# Servos_controller.net
KiCad netlist of a schematic drawn in Altium Designer
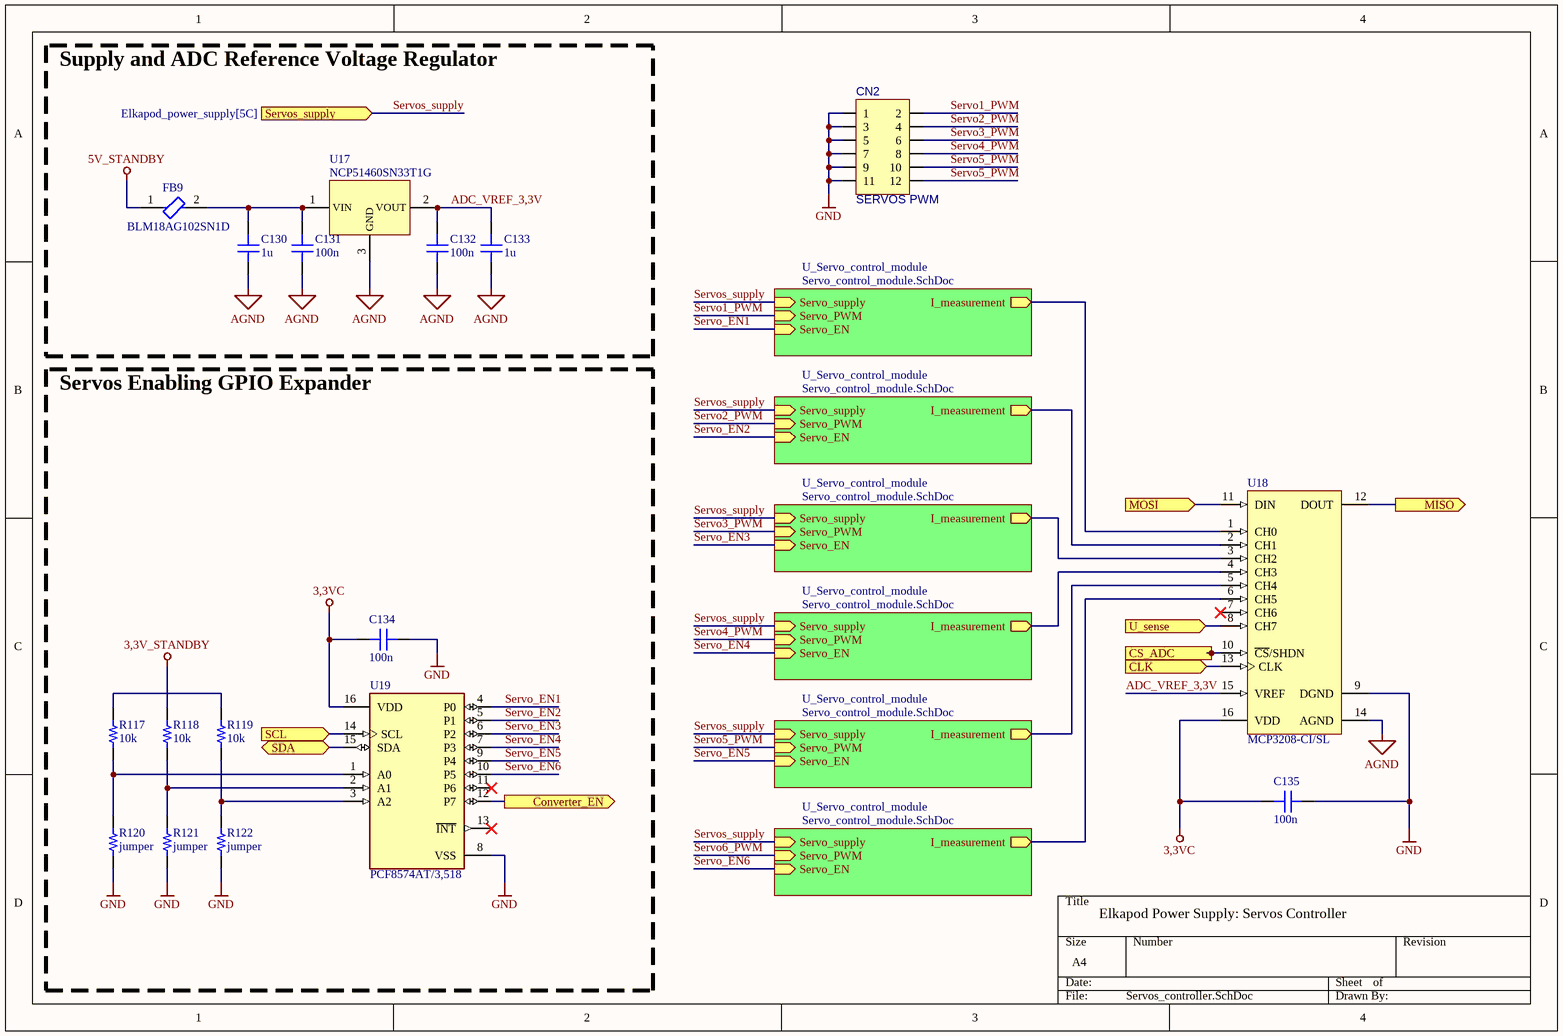
[diagram p0: Servos_controller.SchDoc]

(export (version "E")
  (design (tool "Eeschema 10.0.6"))
  (components
    (comp (ref "C130")
      (value "1u")
      (footprint "CAP 0603_1608")
      (description "CAP CER 1uF 16V X5R 0603")
      (fields (field (name "PART NUMBER") "C0603C272F3GAC7867") (field (name "MANUFACTURER") "KEMET"))
      (libsource (lib "Celestial Altium Library - altium_library") (part "Capacitor"))
    )
    (comp (ref "C131")
      (value "100n")
      (footprint "CAP 0603_1608")
      (description "CAP CER 100nF 25V X5R 0603")
      (fields (field (name "PART NUMBER") "C0603C272F3GAC7867") (field (name "MANUFACTURER") "KEMET"))
      (libsource (lib "Celestial Altium Library - altium_library") (part "Capacitor"))
    )
    (comp (ref "C132")
      (value "100n")
      (footprint "CAP 0603_1608")
      (description "CAP CER 100nF 25V X5R 0603")
      (fields (field (name "PART NUMBER") "C0603C272F3GAC7867") (field (name "MANUFACTURER") "KEMET"))
      (libsource (lib "Celestial Altium Library - altium_library") (part "Capacitor"))
    )
    (comp (ref "C133")
      (value "1u")
      (footprint "CAP 0603_1608")
      (description "CAP CER 1uF 16V X5R 0603")
      (fields (field (name "PART NUMBER") "C0603C272F3GAC7867") (field (name "MANUFACTURER") "KEMET"))
      (libsource (lib "Celestial Altium Library - altium_library") (part "Capacitor"))
    )
    (comp (ref "C134")
      (value "100n")
      (footprint "CAP 0603_1608")
      (description "CAP CER 100nF 25V X5R 0603")
      (fields (field (name "PART NUMBER") "C0603C272F3GAC7867") (field (name "MANUFACTURER") "KEMET"))
      (libsource (lib "Celestial Altium Library - altium_library") (part "Capacitor"))
    )
    (comp (ref "C135")
      (value "100n")
      (footprint "CAP 0603_1608")
      (description "CAP CER 100nF 25V X5R 0603")
      (fields (field (name "PART NUMBER") "C0603C272F3GAC7867") (field (name "MANUFACTURER") "KEMET"))
      (libsource (lib "Celestial Altium Library - altium_library") (part "Capacitor"))
    )
    (comp (ref "CN2") (value "SERVOS PWM") (footprint "IDC12") (libsource (lib "idc") (part "CN_6x2")))
    (comp (ref "FB9")
      (value "BLM18AG102SN1D")
      (footprint "FP-BLM18-0_15-t0_8-MFG")
      (description "Chip Ferrite Bead, 0603, 1000Ω @ 100MHz, 0.5Ω, 25%, 450mA")
      (fields (field (name "TOLERANCE") "25%"))
      (libsource (lib "Altium Content Vault") (part "5f30dd21d616792df468990f7003faa"))
    )
    (comp (ref "R117")
      (value "10k")
      (footprint "RES 0603_1608")
      (description "RES 10K OHM 1% 0,1W 0603")
      (fields
        (field (name "PART NUMBER") "RNCS0603BKE10K0")
        (field (name "MANUFACTURER") "Stackpole Electronics Inc")
      )
      (libsource (lib "Celestial Altium Library - altium_library") (part "Resistor"))
    )
    (comp (ref "R118")
      (value "10k")
      (footprint "RES 0603_1608")
      (description "RES 10K OHM 1% 0,1W 0603")
      (fields
        (field (name "PART NUMBER") "RNCS0603BKE10K0")
        (field (name "MANUFACTURER") "Stackpole Electronics Inc")
      )
      (libsource (lib "Celestial Altium Library - altium_library") (part "Resistor"))
    )
    (comp (ref "R119")
      (value "10k")
      (footprint "RES 0603_1608")
      (description "RES 10K OHM 1% 0,1W 0603")
      (fields
        (field (name "PART NUMBER") "RNCS0603BKE10K0")
        (field (name "MANUFACTURER") "Stackpole Electronics Inc")
      )
      (libsource (lib "Celestial Altium Library - altium_library") (part "Resistor"))
    )
    (comp (ref "R120")
      (value "jumper")
      (footprint "RES 0603_1608")
      (description "RES 0 OHM 1% 0,1W 0603")
      (fields
        (field (name "PART NUMBER") "RNCS0603BKE10K0")
        (field (name "MANUFACTURER") "Stackpole Electronics Inc")
      )
      (libsource (lib "Celestial Altium Library - altium_library") (part "Resistor"))
    )
    (comp (ref "R121")
      (value "jumper")
      (footprint "RES 0603_1608")
      (description "RES 0 OHM 1% 0,1W 0603")
      (fields
        (field (name "PART NUMBER") "RNCS0603BKE10K0")
        (field (name "MANUFACTURER") "Stackpole Electronics Inc")
      )
      (libsource (lib "Celestial Altium Library - altium_library") (part "Resistor"))
    )
    (comp (ref "R122")
      (value "jumper")
      (footprint "RES 0603_1608")
      (description "RES 0 OHM 1% 0,1W 0603")
      (fields
        (field (name "PART NUMBER") "RNCS0603BKE10K0")
        (field (name "MANUFACTURER") "Stackpole Electronics Inc")
      )
      (libsource (lib "Celestial Altium Library - altium_library") (part "Resistor"))
    )
    (comp (ref "U17")
      (value "NCP51460SN33T1G")
      (footprint "SOT23-3")
      (description "Low power precision voltage reference; Iout = 20mA")
      (libsource (lib "My_voltage_regulators") (part "NCP51460SN33T1G"))
    )
    (comp (ref "U18")
      (value "MCP3208-CI/SL")
      (footprint "SOIC-SL16_M")
      (libsource (lib "Altium Content Vault") (part "CON-ADC-MCP3008-16"))
    )
    (comp (ref "U19")
      (value "PCF8574AT/3,518")
      (footprint "FP-SOT162-1-MFG")
      (description "IC I/O EXPANDER I2C 8B 16SOIC")
      (fields
        (field (name "MANUFACTURER") "NXP Semiconductors")
        (field (name "OCTOPART") "https://octopart.com/pcf8574at%2F3%2C518-nxp+semiconductors-11541925")
      )
      (libsource (lib "Altium Content Vault") (part "f7fde53ce59de981fb0b266a4e103eb"))
    )
  )
  (nets
    (net (code "1") (name "/ADC_VREF_3,3V") (class "Default")
      (node (ref "C132") (pin "2") (pinfunction "2_2") (pintype "passive"))
      (node (ref "C133") (pin "2") (pinfunction "2_2") (pintype "passive"))
      (node (ref "U17") (pin "2") (pinfunction "VOUT_2") (pintype "passive"))
      (node (ref "U18") (pin "15") (pinfunction "VREF_15") (pintype "input"))
    )
    (net (code "2") (name "/CLK") (class "Default")
      (node (ref "U18") (pin "13") (pinfunction "CLK_13") (pintype "input"))
    )
    (net (code "3") (name "/CS_ADC") (class "Default")
      (node (ref "U18") (pin "10") (pinfunction "~{CS}/SHDN_10") (pintype "input"))
    )
    (net (code "4") (name "/Converter_EN") (class "Default")
      (node (ref "U19") (pin "12") (pinfunction "P7_12") (pintype "bidirectional"))
    )
    (net (code "5") (name "/I_measurement") (class "Default")
      (node (ref "U18") (pin "3") (pinfunction "CH2_3") (pintype "input"))
    )
    (net (code "6") (name "/I_measurement_1") (class "Default")
      (node (ref "U18") (pin "4") (pinfunction "CH3_4") (pintype "input"))
    )
    (net (code "7") (name "/I_measurement_2") (class "Default")
      (node (ref "U18") (pin "5") (pinfunction "CH4_5") (pintype "input"))
    )
    (net (code "8") (name "/I_measurement_3") (class "Default")
      (node (ref "U18") (pin "6") (pinfunction "CH5_6") (pintype "input"))
    )
    (net (code "9") (name "/I_measurement_4") (class "Default")
      (node (ref "U18") (pin "1") (pinfunction "CH0_1") (pintype "input"))
    )
    (net (code "10") (name "/I_measurement_5") (class "Default")
      (node (ref "U18") (pin "2") (pinfunction "CH1_2") (pintype "input"))
    )
    (net (code "11") (name "/MISO") (class "Default")
      (node (ref "U18") (pin "12") (pinfunction "DOUT_12") (pintype "tri_state"))
    )
    (net (code "12") (name "/MOSI") (class "Default")
      (node (ref "U18") (pin "11") (pinfunction "DIN_11") (pintype "input"))
    )
    (net (code "13") (name "/SCL") (class "Default")
      (node (ref "U19") (pin "14") (pinfunction "SCL_14") (pintype "input"))
    )
    (net (code "14") (name "/SDA") (class "Default")
      (node (ref "U19") (pin "15") (pinfunction "SDA_15") (pintype "bidirectional"))
    )
    (net (code "15") (name "/Servo1_PWM") (class "Default")
      (node (ref "CN2") (pin "2") (pinfunction "2_2") (pintype "passive"))
    )
    (net (code "16") (name "/Servo2_PWM") (class "Default")
      (node (ref "CN2") (pin "4") (pinfunction "4_4") (pintype "passive"))
    )
    (net (code "17") (name "/Servo3_PWM") (class "Default")
      (node (ref "CN2") (pin "6") (pinfunction "6_6") (pintype "passive"))
    )
    (net (code "18") (name "/Servo4_PWM") (class "Default")
      (node (ref "CN2") (pin "8") (pinfunction "8_8") (pintype "passive"))
    )
    (net (code "19") (name "/Servo5_PWM") (class "Default")
      (node (ref "CN2") (pin "10") (pinfunction "10_10") (pintype "passive"))
      (node (ref "CN2") (pin "12") (pinfunction "12_12") (pintype "passive"))
    )
    (net (code "21") (name "/Servo_EN1") (class "Default")
      (node (ref "U19") (pin "4") (pinfunction "P0_4") (pintype "bidirectional"))
    )
    (net (code "22") (name "/Servo_EN2") (class "Default")
      (node (ref "U19") (pin "5") (pinfunction "P1_5") (pintype "bidirectional"))
    )
    (net (code "23") (name "/Servo_EN3") (class "Default")
      (node (ref "U19") (pin "6") (pinfunction "P2_6") (pintype "bidirectional"))
    )
    (net (code "24") (name "/Servo_EN4") (class "Default")
      (node (ref "U19") (pin "7") (pinfunction "P3_7") (pintype "bidirectional"))
    )
    (net (code "25") (name "/Servo_EN5") (class "Default")
      (node (ref "U19") (pin "9") (pinfunction "P4_9") (pintype "bidirectional"))
    )
    (net (code "26") (name "/Servo_EN6") (class "Default")
      (node (ref "U19") (pin "10") (pinfunction "P5_10") (pintype "bidirectional"))
    )
    (net (code "28") (name "/U_sense") (class "Default")
      (node (ref "U18") (pin "8") (pinfunction "CH7_8") (pintype "input"))
    )
    (net (code "29") (name "3,3VC") (class "Default")
      (node (ref "C134") (pin "2") (pinfunction "2_2") (pintype "passive"))
      (node (ref "C135") (pin "2") (pinfunction "2_2") (pintype "passive"))
      (node (ref "U18") (pin "16") (pinfunction "VDD_16") (pintype "power_in"))
      (node (ref "U19") (pin "16") (pinfunction "VDD_16") (pintype "power_in"))
    )
    (net (code "30") (name "3,3V_STANDBY") (class "Default")
      (node (ref "R118") (pin "1") (pinfunction "1_1") (pintype "passive"))
    )
    (net (code "31") (name "5V_STANDBY") (class "Default")
      (node (ref "FB9") (pin "1") (pinfunction "1_1") (pintype "passive"))
    )
    (net (code "32") (name "AGND") (class "Default")
      (node (ref "C130") (pin "1") (pinfunction "1_1") (pintype "passive"))
      (node (ref "C131") (pin "1") (pinfunction "1_1") (pintype "passive"))
      (node (ref "C132") (pin "1") (pinfunction "1_1") (pintype "passive"))
      (node (ref "C133") (pin "1") (pinfunction "1_1") (pintype "passive"))
      (node (ref "U17") (pin "3") (pinfunction "GND_3") (pintype "passive"))
      (node (ref "U18") (pin "14") (pinfunction "AGND_14") (pintype "power_in"))
    )
    (net (code "33") (name "GND") (class "Default")
      (node (ref "C134") (pin "1") (pinfunction "1_1") (pintype "passive"))
      (node (ref "C135") (pin "1") (pinfunction "1_1") (pintype "passive"))
      (node (ref "CN2") (pin "1") (pinfunction "1_1") (pintype "passive"))
      (node (ref "CN2") (pin "11") (pinfunction "11_11") (pintype "passive"))
      (node (ref "CN2") (pin "3") (pinfunction "3_3") (pintype "passive"))
      (node (ref "CN2") (pin "5") (pinfunction "5_5") (pintype "passive"))
      (node (ref "CN2") (pin "7") (pinfunction "7_7") (pintype "passive"))
      (node (ref "CN2") (pin "9") (pinfunction "9_9") (pintype "passive"))
      (node (ref "R120") (pin "2") (pinfunction "2_2") (pintype "passive"))
      (node (ref "R121") (pin "2") (pinfunction "2_2") (pintype "passive"))
      (node (ref "R122") (pin "2") (pinfunction "2_2") (pintype "passive"))
      (node (ref "U18") (pin "9") (pinfunction "DGND_9") (pintype "power_in"))
      (node (ref "U19") (pin "8") (pinfunction "VSS_8") (pintype "power_in"))
    )
    (net (code "34") (name "Net-(R117-Pad1)") (class "Default")
      (node (ref "R117") (pin "1") (pinfunction "1_1") (pintype "passive"))
      (node (ref "R119") (pin "1") (pinfunction "1_1") (pintype "passive"))
    )
    (net (code "35") (name "Net-(U17-VIN)") (class "Default")
      (node (ref "C130") (pin "2") (pinfunction "2_2") (pintype "passive"))
      (node (ref "C131") (pin "2") (pinfunction "2_2") (pintype "passive"))
      (node (ref "FB9") (pin "2") (pinfunction "2_2") (pintype "passive"))
      (node (ref "U17") (pin "1") (pinfunction "VIN_1") (pintype "passive"))
    )
    (net (code "36") (name "Net-(U19-A0)") (class "Default")
      (node (ref "R117") (pin "2") (pinfunction "2_2") (pintype "passive"))
      (node (ref "R120") (pin "1") (pinfunction "1_1") (pintype "passive"))
      (node (ref "U19") (pin "1") (pinfunction "A0_1") (pintype "input"))
    )
    (net (code "37") (name "Net-(U19-A1)") (class "Default")
      (node (ref "R118") (pin "2") (pinfunction "2_2") (pintype "passive"))
      (node (ref "R121") (pin "1") (pinfunction "1_1") (pintype "passive"))
      (node (ref "U19") (pin "2") (pinfunction "A1_2") (pintype "input"))
    )
    (net (code "38") (name "Net-(U19-A2)") (class "Default")
      (node (ref "R119") (pin "2") (pinfunction "2_2") (pintype "passive"))
      (node (ref "R122") (pin "1") (pinfunction "1_1") (pintype "passive"))
      (node (ref "U19") (pin "3") (pinfunction "A2_3") (pintype "input"))
    )
    (net (code "39") (name "unconnected-(U18-CH6-Pad7)") (class "Default")
      (node (ref "U18") (pin "7") (pinfunction "CH6_7") (pintype "input+no_connect"))
    )
    (net (code "40") (name "unconnected-(U19-P6-Pad11)") (class "Default")
      (node (ref "U19") (pin "11") (pinfunction "P6_11") (pintype "bidirectional+no_connect"))
    )
    (net (code "41") (name "unconnected-(U19-~{INT}-Pad13)") (class "Default")
      (node (ref "U19") (pin "13") (pinfunction "~{INT}_13") (pintype "output+no_connect"))
    )
  )
)
